# Digital_Input.net
KiCad netlist of a schematic drawn in Altium Designer
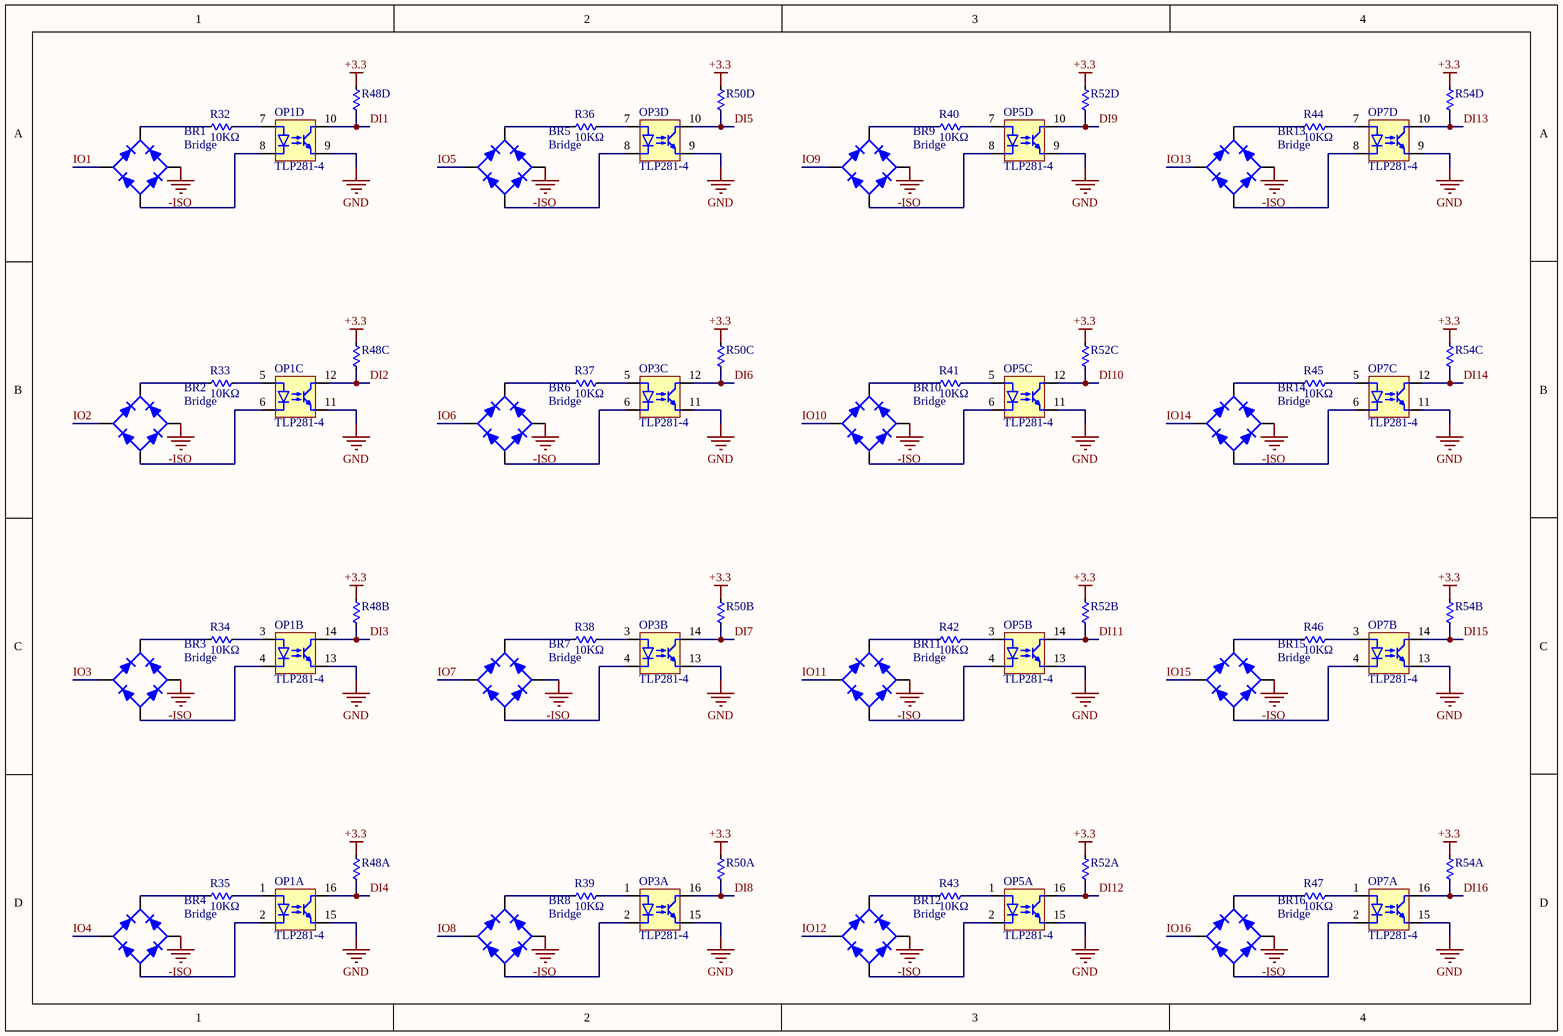
[diagram p0: Digital Input.SchDoc]

(export (version "E")
  (design (tool "Eeschema 10.0.6"))
  (components
    (comp (ref "BR1")
      (value "Bridge")
      (footprint "SOP254P690X270-4L")
      (libsource (lib "Shahnahad") (part "Bridge"))
    )
    (comp (ref "BR2")
      (value "Bridge")
      (footprint "SOP254P690X270-4L")
      (libsource (lib "Shahnahad") (part "Bridge"))
    )
    (comp (ref "BR3")
      (value "Bridge")
      (footprint "SOP254P690X270-4L")
      (libsource (lib "Shahnahad") (part "Bridge"))
    )
    (comp (ref "BR4")
      (value "Bridge")
      (footprint "SOP254P690X270-4L")
      (libsource (lib "Shahnahad") (part "Bridge"))
    )
    (comp (ref "BR5")
      (value "Bridge")
      (footprint "SOP254P690X270-4L")
      (libsource (lib "Shahnahad") (part "Bridge"))
    )
    (comp (ref "BR6")
      (value "Bridge")
      (footprint "SOP254P690X270-4L")
      (libsource (lib "Shahnahad") (part "Bridge"))
    )
    (comp (ref "BR7")
      (value "Bridge")
      (footprint "SOP254P690X270-4L")
      (libsource (lib "Shahnahad") (part "Bridge"))
    )
    (comp (ref "BR8")
      (value "Bridge")
      (footprint "SOP254P690X270-4L")
      (libsource (lib "Shahnahad") (part "Bridge"))
    )
    (comp (ref "BR9")
      (value "Bridge")
      (footprint "SOP254P690X270-4L")
      (libsource (lib "Shahnahad") (part "Bridge"))
    )
    (comp (ref "BR10")
      (value "Bridge")
      (footprint "SOP254P690X270-4L")
      (libsource (lib "Shahnahad") (part "Bridge"))
    )
    (comp (ref "BR11")
      (value "Bridge")
      (footprint "SOP254P690X270-4L")
      (libsource (lib "Shahnahad") (part "Bridge"))
    )
    (comp (ref "BR12")
      (value "Bridge")
      (footprint "SOP254P690X270-4L")
      (libsource (lib "Shahnahad") (part "Bridge"))
    )
    (comp (ref "BR13")
      (value "Bridge")
      (footprint "SOP254P690X270-4L")
      (libsource (lib "Shahnahad") (part "Bridge"))
    )
    (comp (ref "BR14")
      (value "Bridge")
      (footprint "SOP254P690X270-4L")
      (libsource (lib "Shahnahad") (part "Bridge"))
    )
    (comp (ref "BR15")
      (value "Bridge")
      (footprint "SOP254P690X270-4L")
      (libsource (lib "Shahnahad") (part "Bridge"))
    )
    (comp (ref "BR16")
      (value "Bridge")
      (footprint "SOP254P690X270-4L")
      (libsource (lib "Shahnahad") (part "Bridge"))
    )
    (comp (ref "OP1")
      (value "TLP281-4")
      (footprint "SO16 TOSHIBA OPTOCOUPLER")
      (libsource (lib "Shahnahad") (part "TLP281-4"))
    )
    (comp (ref "OP3")
      (value "TLP281-4")
      (footprint "SO16 TOSHIBA OPTOCOUPLER")
      (libsource (lib "Shahnahad") (part "TLP281-4"))
    )
    (comp (ref "OP5")
      (value "TLP281-4")
      (footprint "SO16 TOSHIBA OPTOCOUPLER")
      (libsource (lib "Shahnahad") (part "TLP281-4"))
    )
    (comp (ref "OP7")
      (value "TLP281-4")
      (footprint "SO16 TOSHIBA OPTOCOUPLER")
      (libsource (lib "Shahnahad") (part "TLP281-4"))
    )
    (comp (ref "R32")
      (value "10KΩ")
      (footprint "RES 0603 10K")
      (libsource (lib "Shahnahad") (part "RES 10K"))
    )
    (comp (ref "R33")
      (value "10KΩ")
      (footprint "RES 0603 10K")
      (libsource (lib "Shahnahad") (part "RES 10K"))
    )
    (comp (ref "R34")
      (value "10KΩ")
      (footprint "RES 0603 10K")
      (libsource (lib "Shahnahad") (part "RES 10K"))
    )
    (comp (ref "R35")
      (value "10KΩ")
      (footprint "RES 0603 10K")
      (libsource (lib "Shahnahad") (part "RES 10K"))
    )
    (comp (ref "R36")
      (value "10KΩ")
      (footprint "RES 0603 10K")
      (libsource (lib "Shahnahad") (part "RES 10K"))
    )
    (comp (ref "R37")
      (value "10KΩ")
      (footprint "RES 0603 10K")
      (libsource (lib "Shahnahad") (part "RES 10K"))
    )
    (comp (ref "R38")
      (value "10KΩ")
      (footprint "RES 0603 10K")
      (libsource (lib "Shahnahad") (part "RES 10K"))
    )
    (comp (ref "R39")
      (value "10KΩ")
      (footprint "RES 0603 10K")
      (libsource (lib "Shahnahad") (part "RES 10K"))
    )
    (comp (ref "R40")
      (value "10KΩ")
      (footprint "RES 0603 10K")
      (libsource (lib "Shahnahad") (part "RES 10K"))
    )
    (comp (ref "R41")
      (value "10KΩ")
      (footprint "RES 0603 10K")
      (libsource (lib "Shahnahad") (part "RES 10K"))
    )
    (comp (ref "R42")
      (value "10KΩ")
      (footprint "RES 0603 10K")
      (libsource (lib "Shahnahad") (part "RES 10K"))
    )
    (comp (ref "R43")
      (value "10KΩ")
      (footprint "RES 0603 10K")
      (libsource (lib "Shahnahad") (part "RES 10K"))
    )
    (comp (ref "R44")
      (value "10KΩ")
      (footprint "RES 0603 10K")
      (libsource (lib "Shahnahad") (part "RES 10K"))
    )
    (comp (ref "R45")
      (value "10KΩ")
      (footprint "RES 0603 10K")
      (libsource (lib "Shahnahad") (part "RES 10K"))
    )
    (comp (ref "R46")
      (value "10KΩ")
      (footprint "RES 0603 10K")
      (libsource (lib "Shahnahad") (part "RES 10K"))
    )
    (comp (ref "R47")
      (value "10KΩ")
      (footprint "RES 0603 10K")
      (libsource (lib "Shahnahad") (part "RES 10K"))
    )
    (comp (ref "R48")
      (value "10KΩ")
      (footprint "RES ARRAY 4X0603 10K")
      (libsource (lib "Shahnahad") (part "RES ARRAY 10K"))
    )
    (comp (ref "R50")
      (value "10KΩ")
      (footprint "RES ARRAY 4X0603 10K")
      (libsource (lib "Shahnahad") (part "RES ARRAY 10K"))
    )
    (comp (ref "R52")
      (value "10KΩ")
      (footprint "RES ARRAY 4X0603 10K")
      (libsource (lib "Shahnahad") (part "RES ARRAY 10K"))
    )
    (comp (ref "R54")
      (value "10KΩ")
      (footprint "RES ARRAY 4X0603 10K")
      (libsource (lib "Shahnahad") (part "RES ARRAY 10K"))
    )
  )
  (nets
    (net (code "1") (name "+3.3") (class "Default")
      (node (ref "R48") (pin "5") (pintype "passive"))
      (node (ref "R48") (pin "6") (pintype "passive"))
      (node (ref "R48") (pin "7") (pintype "passive"))
      (node (ref "R48") (pin "8") (pintype "passive"))
      (node (ref "R50") (pin "5") (pintype "passive"))
      (node (ref "R50") (pin "6") (pintype "passive"))
      (node (ref "R50") (pin "7") (pintype "passive"))
      (node (ref "R50") (pin "8") (pintype "passive"))
      (node (ref "R52") (pin "5") (pintype "passive"))
      (node (ref "R52") (pin "6") (pintype "passive"))
      (node (ref "R52") (pin "7") (pintype "passive"))
      (node (ref "R52") (pin "8") (pintype "passive"))
      (node (ref "R54") (pin "5") (pintype "passive"))
      (node (ref "R54") (pin "6") (pintype "passive"))
      (node (ref "R54") (pin "7") (pintype "passive"))
      (node (ref "R54") (pin "8") (pintype "passive"))
    )
    (net (code "2") (name "-ISO") (class "Default")
      (node (ref "BR1") (pin "4") (pinfunction "~_4") (pintype "passive"))
      (node (ref "BR10") (pin "4") (pinfunction "~_4") (pintype "passive"))
      (node (ref "BR11") (pin "4") (pinfunction "~_4") (pintype "passive"))
      (node (ref "BR12") (pin "4") (pinfunction "~_4") (pintype "passive"))
      (node (ref "BR13") (pin "4") (pinfunction "~_4") (pintype "passive"))
      (node (ref "BR14") (pin "4") (pinfunction "~_4") (pintype "passive"))
      (node (ref "BR15") (pin "4") (pinfunction "~_4") (pintype "passive"))
      (node (ref "BR16") (pin "4") (pinfunction "~_4") (pintype "passive"))
      (node (ref "BR2") (pin "4") (pinfunction "~_4") (pintype "passive"))
      (node (ref "BR3") (pin "4") (pinfunction "~_4") (pintype "passive"))
      (node (ref "BR4") (pin "4") (pinfunction "~_4") (pintype "passive"))
      (node (ref "BR5") (pin "4") (pinfunction "~_4") (pintype "passive"))
      (node (ref "BR6") (pin "4") (pinfunction "~_4") (pintype "passive"))
      (node (ref "BR7") (pin "4") (pinfunction "~_4") (pintype "passive"))
      (node (ref "BR8") (pin "4") (pinfunction "~_4") (pintype "passive"))
      (node (ref "BR9") (pin "4") (pinfunction "~_4") (pintype "passive"))
    )
    (net (code "3") (name "/DI1") (class "Default")
      (node (ref "OP1") (pin "10") (pinfunction "10_10") (pintype "passive"))
      (node (ref "R48") (pin "4") (pintype "passive"))
    )
    (net (code "4") (name "/DI2") (class "Default")
      (node (ref "OP1") (pin "12") (pinfunction "12_12") (pintype "passive"))
      (node (ref "R48") (pin "3") (pintype "passive"))
    )
    (net (code "5") (name "/DI3") (class "Default")
      (node (ref "OP1") (pin "14") (pinfunction "14_14") (pintype "passive"))
      (node (ref "R48") (pin "2") (pintype "passive"))
    )
    (net (code "6") (name "/DI4") (class "Default")
      (node (ref "OP1") (pin "16") (pinfunction "16_16") (pintype "passive"))
      (node (ref "R48") (pin "1") (pintype "passive"))
    )
    (net (code "7") (name "/DI5") (class "Default")
      (node (ref "OP3") (pin "10") (pinfunction "10_10") (pintype "passive"))
      (node (ref "R50") (pin "4") (pintype "passive"))
    )
    (net (code "8") (name "/DI6") (class "Default")
      (node (ref "OP3") (pin "12") (pinfunction "12_12") (pintype "passive"))
      (node (ref "R50") (pin "3") (pintype "passive"))
    )
    (net (code "9") (name "/DI7") (class "Default")
      (node (ref "OP3") (pin "14") (pinfunction "14_14") (pintype "passive"))
      (node (ref "R50") (pin "2") (pintype "passive"))
    )
    (net (code "10") (name "/DI8") (class "Default")
      (node (ref "OP3") (pin "16") (pinfunction "16_16") (pintype "passive"))
      (node (ref "R50") (pin "1") (pintype "passive"))
    )
    (net (code "11") (name "/DI9") (class "Default")
      (node (ref "OP5") (pin "10") (pinfunction "10_10") (pintype "passive"))
      (node (ref "R52") (pin "4") (pintype "passive"))
    )
    (net (code "12") (name "/DI10") (class "Default")
      (node (ref "OP5") (pin "12") (pinfunction "12_12") (pintype "passive"))
      (node (ref "R52") (pin "3") (pintype "passive"))
    )
    (net (code "13") (name "/DI11") (class "Default")
      (node (ref "OP5") (pin "14") (pinfunction "14_14") (pintype "passive"))
      (node (ref "R52") (pin "2") (pintype "passive"))
    )
    (net (code "14") (name "/DI12") (class "Default")
      (node (ref "OP5") (pin "16") (pinfunction "16_16") (pintype "passive"))
      (node (ref "R52") (pin "1") (pintype "passive"))
    )
    (net (code "15") (name "/DI13") (class "Default")
      (node (ref "OP7") (pin "10") (pinfunction "10_10") (pintype "passive"))
      (node (ref "R54") (pin "4") (pintype "passive"))
    )
    (net (code "16") (name "/DI14") (class "Default")
      (node (ref "OP7") (pin "12") (pinfunction "12_12") (pintype "passive"))
      (node (ref "R54") (pin "3") (pintype "passive"))
    )
    (net (code "17") (name "/DI15") (class "Default")
      (node (ref "OP7") (pin "14") (pinfunction "14_14") (pintype "passive"))
      (node (ref "R54") (pin "2") (pintype "passive"))
    )
    (net (code "18") (name "/DI16") (class "Default")
      (node (ref "OP7") (pin "16") (pinfunction "16_16") (pintype "passive"))
      (node (ref "R54") (pin "1") (pintype "passive"))
    )
    (net (code "19") (name "/IO1") (class "Default")
      (node (ref "BR1") (pin "3") (pinfunction "~_3") (pintype "passive"))
    )
    (net (code "20") (name "/IO2") (class "Default")
      (node (ref "BR2") (pin "3") (pinfunction "~_3") (pintype "passive"))
    )
    (net (code "21") (name "/IO3") (class "Default")
      (node (ref "BR3") (pin "3") (pinfunction "~_3") (pintype "passive"))
    )
    (net (code "22") (name "/IO4") (class "Default")
      (node (ref "BR4") (pin "3") (pinfunction "~_3") (pintype "passive"))
    )
    (net (code "23") (name "/IO5") (class "Default")
      (node (ref "BR5") (pin "3") (pinfunction "~_3") (pintype "passive"))
    )
    (net (code "24") (name "/IO6") (class "Default")
      (node (ref "BR6") (pin "3") (pinfunction "~_3") (pintype "passive"))
    )
    (net (code "25") (name "/IO7") (class "Default")
      (node (ref "BR7") (pin "3") (pinfunction "~_3") (pintype "passive"))
    )
    (net (code "26") (name "/IO8") (class "Default")
      (node (ref "BR8") (pin "3") (pinfunction "~_3") (pintype "passive"))
    )
    (net (code "27") (name "/IO9") (class "Default")
      (node (ref "BR9") (pin "3") (pinfunction "~_3") (pintype "passive"))
    )
    (net (code "28") (name "/IO10") (class "Default")
      (node (ref "BR10") (pin "3") (pinfunction "~_3") (pintype "passive"))
    )
    (net (code "29") (name "/IO11") (class "Default")
      (node (ref "BR11") (pin "3") (pinfunction "~_3") (pintype "passive"))
    )
    (net (code "30") (name "/IO12") (class "Default")
      (node (ref "BR12") (pin "3") (pinfunction "~_3") (pintype "passive"))
    )
    (net (code "31") (name "/IO13") (class "Default")
      (node (ref "BR13") (pin "3") (pinfunction "~_3") (pintype "passive"))
    )
    (net (code "32") (name "/IO14") (class "Default")
      (node (ref "BR14") (pin "3") (pinfunction "~_3") (pintype "passive"))
    )
    (net (code "33") (name "/IO15") (class "Default")
      (node (ref "BR15") (pin "3") (pinfunction "~_3") (pintype "passive"))
    )
    (net (code "34") (name "/IO16") (class "Default")
      (node (ref "BR16") (pin "3") (pinfunction "~_3") (pintype "passive"))
    )
    (net (code "35") (name "GND") (class "Default")
      (node (ref "OP1") (pin "11") (pinfunction "11_11") (pintype "passive"))
      (node (ref "OP1") (pin "13") (pinfunction "13_13") (pintype "passive"))
      (node (ref "OP1") (pin "15") (pinfunction "15_15") (pintype "passive"))
      (node (ref "OP1") (pin "9") (pinfunction "9_9") (pintype "passive"))
      (node (ref "OP3") (pin "11") (pinfunction "11_11") (pintype "passive"))
      (node (ref "OP3") (pin "13") (pinfunction "13_13") (pintype "passive"))
      (node (ref "OP3") (pin "15") (pinfunction "15_15") (pintype "passive"))
      (node (ref "OP3") (pin "9") (pinfunction "9_9") (pintype "passive"))
      (node (ref "OP5") (pin "11") (pinfunction "11_11") (pintype "passive"))
      (node (ref "OP5") (pin "13") (pinfunction "13_13") (pintype "passive"))
      (node (ref "OP5") (pin "15") (pinfunction "15_15") (pintype "passive"))
      (node (ref "OP5") (pin "9") (pinfunction "9_9") (pintype "passive"))
      (node (ref "OP7") (pin "11") (pinfunction "11_11") (pintype "passive"))
      (node (ref "OP7") (pin "13") (pinfunction "13_13") (pintype "passive"))
      (node (ref "OP7") (pin "15") (pinfunction "15_15") (pintype "passive"))
      (node (ref "OP7") (pin "9") (pinfunction "9_9") (pintype "passive"))
    )
    (net (code "36") (name "Net-(BR1-+)") (class "Default")
      (node (ref "BR1") (pin "1") (pinfunction "+_1") (pintype "passive"))
      (node (ref "R32") (pin "1") (pintype "passive"))
    )
    (net (code "37") (name "Net-(BR1--)") (class "Default")
      (node (ref "BR1") (pin "2") (pinfunction "-_2") (pintype "passive"))
      (node (ref "OP1") (pin "8") (pinfunction "8_8") (pintype "passive"))
    )
    (net (code "38") (name "Net-(BR2-+)") (class "Default")
      (node (ref "BR2") (pin "1") (pinfunction "+_1") (pintype "passive"))
      (node (ref "R33") (pin "1") (pintype "passive"))
    )
    (net (code "39") (name "Net-(BR2--)") (class "Default")
      (node (ref "BR2") (pin "2") (pinfunction "-_2") (pintype "passive"))
      (node (ref "OP1") (pin "6") (pinfunction "6_6") (pintype "passive"))
    )
    (net (code "40") (name "Net-(BR3-+)") (class "Default")
      (node (ref "BR3") (pin "1") (pinfunction "+_1") (pintype "passive"))
      (node (ref "R34") (pin "1") (pintype "passive"))
    )
    (net (code "41") (name "Net-(BR3--)") (class "Default")
      (node (ref "BR3") (pin "2") (pinfunction "-_2") (pintype "passive"))
      (node (ref "OP1") (pin "4") (pinfunction "4_4") (pintype "passive"))
    )
    (net (code "42") (name "Net-(BR4-+)") (class "Default")
      (node (ref "BR4") (pin "1") (pinfunction "+_1") (pintype "passive"))
      (node (ref "R35") (pin "1") (pintype "passive"))
    )
    (net (code "43") (name "Net-(BR4--)") (class "Default")
      (node (ref "BR4") (pin "2") (pinfunction "-_2") (pintype "passive"))
      (node (ref "OP1") (pin "2") (pinfunction "2_2") (pintype "passive"))
    )
    (net (code "44") (name "Net-(BR5-+)") (class "Default")
      (node (ref "BR5") (pin "1") (pinfunction "+_1") (pintype "passive"))
      (node (ref "R36") (pin "1") (pintype "passive"))
    )
    (net (code "45") (name "Net-(BR5--)") (class "Default")
      (node (ref "BR5") (pin "2") (pinfunction "-_2") (pintype "passive"))
      (node (ref "OP3") (pin "8") (pinfunction "8_8") (pintype "passive"))
    )
    (net (code "46") (name "Net-(BR6-+)") (class "Default")
      (node (ref "BR6") (pin "1") (pinfunction "+_1") (pintype "passive"))
      (node (ref "R37") (pin "1") (pintype "passive"))
    )
    (net (code "47") (name "Net-(BR6--)") (class "Default")
      (node (ref "BR6") (pin "2") (pinfunction "-_2") (pintype "passive"))
      (node (ref "OP3") (pin "6") (pinfunction "6_6") (pintype "passive"))
    )
    (net (code "48") (name "Net-(BR7-+)") (class "Default")
      (node (ref "BR7") (pin "1") (pinfunction "+_1") (pintype "passive"))
      (node (ref "R38") (pin "1") (pintype "passive"))
    )
    (net (code "49") (name "Net-(BR7--)") (class "Default")
      (node (ref "BR7") (pin "2") (pinfunction "-_2") (pintype "passive"))
      (node (ref "OP3") (pin "4") (pinfunction "4_4") (pintype "passive"))
    )
    (net (code "50") (name "Net-(BR8-+)") (class "Default")
      (node (ref "BR8") (pin "1") (pinfunction "+_1") (pintype "passive"))
      (node (ref "R39") (pin "1") (pintype "passive"))
    )
    (net (code "51") (name "Net-(BR8--)") (class "Default")
      (node (ref "BR8") (pin "2") (pinfunction "-_2") (pintype "passive"))
      (node (ref "OP3") (pin "2") (pinfunction "2_2") (pintype "passive"))
    )
    (net (code "52") (name "Net-(BR9-+)") (class "Default")
      (node (ref "BR9") (pin "1") (pinfunction "+_1") (pintype "passive"))
      (node (ref "R40") (pin "1") (pintype "passive"))
    )
    (net (code "53") (name "Net-(BR9--)") (class "Default")
      (node (ref "BR9") (pin "2") (pinfunction "-_2") (pintype "passive"))
      (node (ref "OP5") (pin "8") (pinfunction "8_8") (pintype "passive"))
    )
    (net (code "54") (name "Net-(BR10-+)") (class "Default")
      (node (ref "BR10") (pin "1") (pinfunction "+_1") (pintype "passive"))
      (node (ref "R41") (pin "1") (pintype "passive"))
    )
    (net (code "55") (name "Net-(BR10--)") (class "Default")
      (node (ref "BR10") (pin "2") (pinfunction "-_2") (pintype "passive"))
      (node (ref "OP5") (pin "6") (pinfunction "6_6") (pintype "passive"))
    )
    (net (code "56") (name "Net-(BR11-+)") (class "Default")
      (node (ref "BR11") (pin "1") (pinfunction "+_1") (pintype "passive"))
      (node (ref "R42") (pin "1") (pintype "passive"))
    )
    (net (code "57") (name "Net-(BR11--)") (class "Default")
      (node (ref "BR11") (pin "2") (pinfunction "-_2") (pintype "passive"))
      (node (ref "OP5") (pin "4") (pinfunction "4_4") (pintype "passive"))
    )
    (net (code "58") (name "Net-(BR12-+)") (class "Default")
      (node (ref "BR12") (pin "1") (pinfunction "+_1") (pintype "passive"))
      (node (ref "R43") (pin "1") (pintype "passive"))
    )
    (net (code "59") (name "Net-(BR12--)") (class "Default")
      (node (ref "BR12") (pin "2") (pinfunction "-_2") (pintype "passive"))
      (node (ref "OP5") (pin "2") (pinfunction "2_2") (pintype "passive"))
    )
    (net (code "60") (name "Net-(BR13-+)") (class "Default")
      (node (ref "BR13") (pin "1") (pinfunction "+_1") (pintype "passive"))
      (node (ref "R44") (pin "1") (pintype "passive"))
    )
    (net (code "61") (name "Net-(BR13--)") (class "Default")
      (node (ref "BR13") (pin "2") (pinfunction "-_2") (pintype "passive"))
      (node (ref "OP7") (pin "8") (pinfunction "8_8") (pintype "passive"))
    )
    (net (code "62") (name "Net-(BR14-+)") (class "Default")
      (node (ref "BR14") (pin "1") (pinfunction "+_1") (pintype "passive"))
      (node (ref "R45") (pin "1") (pintype "passive"))
    )
    (net (code "63") (name "Net-(BR14--)") (class "Default")
      (node (ref "BR14") (pin "2") (pinfunction "-_2") (pintype "passive"))
      (node (ref "OP7") (pin "6") (pinfunction "6_6") (pintype "passive"))
    )
    (net (code "64") (name "Net-(BR15-+)") (class "Default")
      (node (ref "BR15") (pin "1") (pinfunction "+_1") (pintype "passive"))
      (node (ref "R46") (pin "1") (pintype "passive"))
    )
    (net (code "65") (name "Net-(BR15--)") (class "Default")
      (node (ref "BR15") (pin "2") (pinfunction "-_2") (pintype "passive"))
      (node (ref "OP7") (pin "4") (pinfunction "4_4") (pintype "passive"))
    )
    (net (code "66") (name "Net-(BR16-+)") (class "Default")
      (node (ref "BR16") (pin "1") (pinfunction "+_1") (pintype "passive"))
      (node (ref "R47") (pin "1") (pintype "passive"))
    )
    (net (code "67") (name "Net-(BR16--)") (class "Default")
      (node (ref "BR16") (pin "2") (pinfunction "-_2") (pintype "passive"))
      (node (ref "OP7") (pin "2") (pinfunction "2_2") (pintype "passive"))
    )
    (net (code "68") (name "Net-(OP1-Pad1)") (class "Default")
      (node (ref "OP1") (pin "1") (pinfunction "1_1") (pintype "passive"))
      (node (ref "R35") (pin "2") (pintype "passive"))
    )
    (net (code "69") (name "Net-(OP1-Pad3)") (class "Default")
      (node (ref "OP1") (pin "3") (pinfunction "3_3") (pintype "passive"))
      (node (ref "R34") (pin "2") (pintype "passive"))
    )
    (net (code "70") (name "Net-(OP1-Pad5)") (class "Default")
      (node (ref "OP1") (pin "5") (pinfunction "5_5") (pintype "passive"))
      (node (ref "R33") (pin "2") (pintype "passive"))
    )
    (net (code "71") (name "Net-(OP1-Pad7)") (class "Default")
      (node (ref "OP1") (pin "7") (pinfunction "7_7") (pintype "passive"))
      (node (ref "R32") (pin "2") (pintype "passive"))
    )
    (net (code "72") (name "Net-(OP3-Pad1)") (class "Default")
      (node (ref "OP3") (pin "1") (pinfunction "1_1") (pintype "passive"))
      (node (ref "R39") (pin "2") (pintype "passive"))
    )
    (net (code "73") (name "Net-(OP3-Pad3)") (class "Default")
      (node (ref "OP3") (pin "3") (pinfunction "3_3") (pintype "passive"))
      (node (ref "R38") (pin "2") (pintype "passive"))
    )
    (net (code "74") (name "Net-(OP3-Pad5)") (class "Default")
      (node (ref "OP3") (pin "5") (pinfunction "5_5") (pintype "passive"))
      (node (ref "R37") (pin "2") (pintype "passive"))
    )
    (net (code "75") (name "Net-(OP3-Pad7)") (class "Default")
      (node (ref "OP3") (pin "7") (pinfunction "7_7") (pintype "passive"))
      (node (ref "R36") (pin "2") (pintype "passive"))
    )
    (net (code "76") (name "Net-(OP5-Pad1)") (class "Default")
      (node (ref "OP5") (pin "1") (pinfunction "1_1") (pintype "passive"))
      (node (ref "R43") (pin "2") (pintype "passive"))
    )
    (net (code "77") (name "Net-(OP5-Pad3)") (class "Default")
      (node (ref "OP5") (pin "3") (pinfunction "3_3") (pintype "passive"))
      (node (ref "R42") (pin "2") (pintype "passive"))
    )
    (net (code "78") (name "Net-(OP5-Pad5)") (class "Default")
      (node (ref "OP5") (pin "5") (pinfunction "5_5") (pintype "passive"))
      (node (ref "R41") (pin "2") (pintype "passive"))
    )
    (net (code "79") (name "Net-(OP5-Pad7)") (class "Default")
      (node (ref "OP5") (pin "7") (pinfunction "7_7") (pintype "passive"))
      (node (ref "R40") (pin "2") (pintype "passive"))
    )
    (net (code "80") (name "Net-(OP7-Pad1)") (class "Default")
      (node (ref "OP7") (pin "1") (pinfunction "1_1") (pintype "passive"))
      (node (ref "R47") (pin "2") (pintype "passive"))
    )
    (net (code "81") (name "Net-(OP7-Pad3)") (class "Default")
      (node (ref "OP7") (pin "3") (pinfunction "3_3") (pintype "passive"))
      (node (ref "R46") (pin "2") (pintype "passive"))
    )
    (net (code "82") (name "Net-(OP7-Pad5)") (class "Default")
      (node (ref "OP7") (pin "5") (pinfunction "5_5") (pintype "passive"))
      (node (ref "R45") (pin "2") (pintype "passive"))
    )
    (net (code "83") (name "Net-(OP7-Pad7)") (class "Default")
      (node (ref "OP7") (pin "7") (pinfunction "7_7") (pintype "passive"))
      (node (ref "R44") (pin "2") (pintype "passive"))
    )
  )
)
